# 03_LCD.net
KiCad netlist of a schematic drawn in Altium Designer
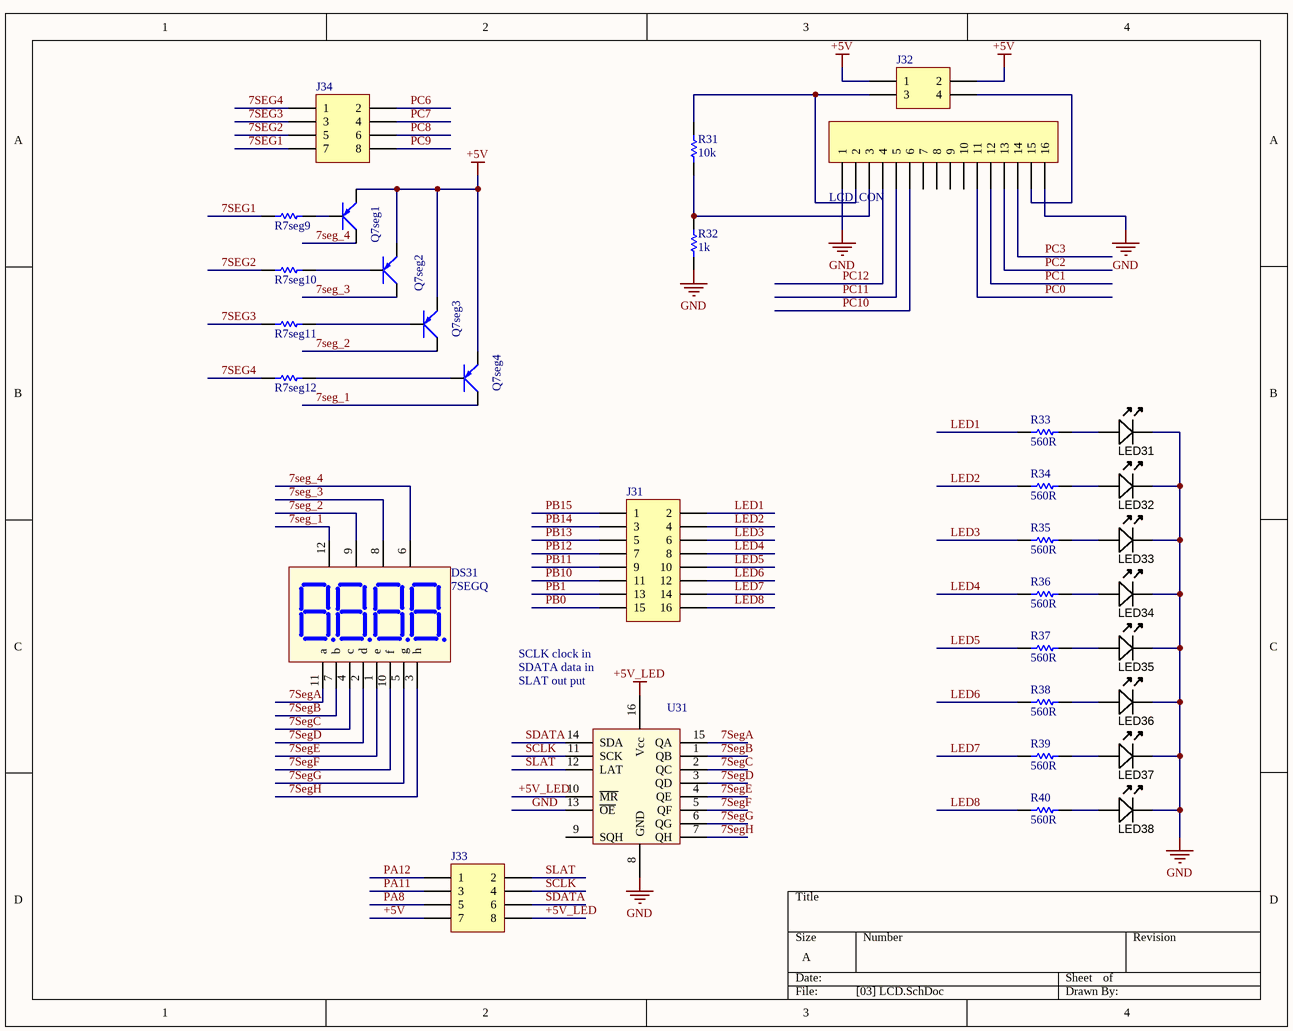
[diagram p0: [03] LCD.SchDoc]

(export (version "E")
  (design (tool "Eeschema 10.0.6"))
  (components
    (comp (ref "DS31")
      (value "7SEGQ")
      (footprint "7segx4_small")
      (description "Four 7 Seg Dipslay")
      (libsource (lib "syhaunguyen") (part "LED7Q"))
    )
    (comp (ref "J31")
      (value "Header 8X2")
      (footprint "HDR2X8")
      (description "Header, 8-Pin, Dual row")
      (fields (field (name "PUBLISHER") "Altium Limited"))
      (libsource (lib "Miscellaneous Connectors") (part "Header 8X2"))
    )
    (comp (ref "J32")
      (value "Header 2X2")
      (footprint "HDR2X2")
      (description "Header, 2-Pin, Dual row")
      (fields (field (name "PUBLISHER") "Altium Limited"))
      (libsource (lib "Miscellaneous Connectors") (part "Header 2X2"))
    )
    (comp (ref "J33")
      (value "Header 4X2")
      (footprint "HDR2X4")
      (description "Header, 4-Pin, Dual row")
      (fields (field (name "PUBLISHER") "Altium Limited"))
      (libsource (lib "Miscellaneous Connectors") (part "Header 4X2"))
    )
    (comp (ref "J34")
      (value "Header 4X2")
      (footprint "HDR2X4")
      (description "Header, 4-Pin, Dual row")
      (fields (field (name "PUBLISHER") "Altium Limited"))
      (libsource (lib "Miscellaneous Connectors") (part "Header 4X2"))
    )
    (comp (ref "LCD_CON")
      (value "Header 16")
      (footprint "HDR1X16")
      (description "Header, 16-Pin")
      (fields (field (name "PUBLISHER") "Altium Limited"))
      (libsource (lib "heromap") (part "Header 16"))
    )
    (comp (ref "LED31")
      (value "Blue")
      (footprint "LED-0805-K")
      (description "LED 0805 SMD Blue 100mcd 470nm")
      (libsource (lib "PBL - Light Sources") (part "LED_SMD_Blue_0805_100mcd"))
    )
    (comp (ref "LED32")
      (value "Blue")
      (footprint "LED-0805-K")
      (description "LED 0805 SMD Blue 100mcd 470nm")
      (libsource (lib "PBL - Light Sources") (part "LED_SMD_Blue_0805_100mcd"))
    )
    (comp (ref "LED33")
      (value "Blue")
      (footprint "LED-0805-K")
      (description "LED 0805 SMD Blue 100mcd 470nm")
      (libsource (lib "PBL - Light Sources") (part "LED_SMD_Blue_0805_100mcd"))
    )
    (comp (ref "LED34")
      (value "Blue")
      (footprint "LED-0805-K")
      (description "LED 0805 SMD Blue 100mcd 470nm")
      (libsource (lib "PBL - Light Sources") (part "LED_SMD_Blue_0805_100mcd"))
    )
    (comp (ref "LED35")
      (value "Blue")
      (footprint "LED-0805-K")
      (description "LED 0805 SMD Blue 100mcd 470nm")
      (libsource (lib "PBL - Light Sources") (part "LED_SMD_Blue_0805_100mcd"))
    )
    (comp (ref "LED36")
      (value "Blue")
      (footprint "LED-0805-K")
      (description "LED 0805 SMD Blue 100mcd 470nm")
      (libsource (lib "PBL - Light Sources") (part "LED_SMD_Blue_0805_100mcd"))
    )
    (comp (ref "LED37")
      (value "Blue")
      (footprint "LED-0805-K")
      (description "LED 0805 SMD Blue 100mcd 470nm")
      (libsource (lib "PBL - Light Sources") (part "LED_SMD_Blue_0805_100mcd"))
    )
    (comp (ref "LED38")
      (value "Blue")
      (footprint "LED-0805-K")
      (description "LED 0805 SMD Blue 100mcd 470nm")
      (libsource (lib "PBL - Light Sources") (part "LED_SMD_Blue_0805_100mcd"))
    )
    (comp (ref "Q7seg1")
      (value "A1015")
      (footprint "SOT23B")
      (description "PNP 600mW, ECB")
      (libsource (lib "syhaunguyen") (part "A1015"))
    )
    (comp (ref "Q7seg2")
      (value "A1015")
      (footprint "SOT23B")
      (description "PNP 600mW, ECB")
      (libsource (lib "syhaunguyen") (part "A1015"))
    )
    (comp (ref "Q7seg3")
      (value "A1015")
      (footprint "SOT23B")
      (description "PNP 600mW, ECB")
      (libsource (lib "syhaunguyen") (part "A1015"))
    )
    (comp (ref "Q7seg4")
      (value "A1015")
      (footprint "SOT23B")
      (description "PNP 600mW, ECB")
      (libsource (lib "syhaunguyen") (part "A1015"))
    )
    (comp (ref "R7seg9") (value "Res") (footprint "RESC1608N_ZERO") (libsource (lib "Tuan") (part "Res")))
    (comp (ref "R7seg10") (value "Res") (footprint "RESC1608N_ZERO") (libsource (lib "Tuan") (part "Res")))
    (comp (ref "R7seg11") (value "Res") (footprint "RESC1608N_ZERO") (libsource (lib "Tuan") (part "Res")))
    (comp (ref "R7seg12") (value "Res") (footprint "RESC1608N_ZERO") (libsource (lib "Tuan") (part "Res")))
    (comp (ref "R31")
      (value "10k")
      (footprint "RESC1608N_ZERO")
      (fields (field (name "Comment") "Res"))
      (libsource (lib "Tuan") (part "Res"))
    )
    (comp (ref "R32")
      (value "1k")
      (footprint "RESC1608N_ZERO")
      (fields (field (name "Comment") "Res"))
      (libsource (lib "Tuan") (part "Res"))
    )
    (comp (ref "R33")
      (value "560R")
      (footprint "RESC1608N_ZERO")
      (fields (field (name "Comment") "Res"))
      (libsource (lib "Tuan") (part "Res"))
    )
    (comp (ref "R34")
      (value "560R")
      (footprint "RESC1608N_ZERO")
      (fields (field (name "Comment") "Res"))
      (libsource (lib "Tuan") (part "Res"))
    )
    (comp (ref "R35")
      (value "560R")
      (footprint "RESC1608N_ZERO")
      (fields (field (name "Comment") "Res"))
      (libsource (lib "Tuan") (part "Res"))
    )
    (comp (ref "R36")
      (value "560R")
      (footprint "RESC1608N_ZERO")
      (fields (field (name "Comment") "Res"))
      (libsource (lib "Tuan") (part "Res"))
    )
    (comp (ref "R37")
      (value "560R")
      (footprint "RESC1608N_ZERO")
      (fields (field (name "Comment") "Res"))
      (libsource (lib "Tuan") (part "Res"))
    )
    (comp (ref "R38")
      (value "560R")
      (footprint "RESC1608N_ZERO")
      (fields (field (name "Comment") "Res"))
      (libsource (lib "Tuan") (part "Res"))
    )
    (comp (ref "R39")
      (value "560R")
      (footprint "RESC1608N_ZERO")
      (fields (field (name "Comment") "Res"))
      (libsource (lib "Tuan") (part "Res"))
    )
    (comp (ref "R40")
      (value "560R")
      (footprint "RESC1608N_ZERO")
      (fields (field (name "Comment") "Res"))
      (libsource (lib "Tuan") (part "Res"))
    )
    (comp (ref "U31") (value "74HC595") (footprint "SOIC16") (libsource (lib "Tuan") (part "74HC595")))
  )
  (nets
    (net (code "1") (name "+5V") (class "Default")
      (node (ref "J32") (pin "1") (pinfunction "1_1") (pintype "passive"))
      (node (ref "J32") (pin "2") (pinfunction "2_2") (pintype "passive"))
      (node (ref "J33") (pin "7") (pinfunction "7_7") (pintype "passive"))
      (node (ref "Q7seg1") (pin "1") (pinfunction "E_1") (pintype "passive"))
      (node (ref "Q7seg2") (pin "1") (pinfunction "E_1") (pintype "passive"))
      (node (ref "Q7seg3") (pin "1") (pinfunction "E_1") (pintype "passive"))
      (node (ref "Q7seg4") (pin "1") (pinfunction "E_1") (pintype "passive"))
    )
    (net (code "2") (name "+5V_LED") (class "Default")
      (node (ref "J33") (pin "8") (pinfunction "8_8") (pintype "passive"))
      (node (ref "U31") (pin "10") (pinfunction "~{MR}_10") (pintype "passive"))
      (node (ref "U31") (pin "16") (pinfunction "Vcc_16") (pintype "power_in"))
    )
    (net (code "3") (name "/7SEG1") (class "Default")
      (node (ref "J34") (pin "7") (pinfunction "7_7") (pintype "passive"))
      (node (ref "R7seg9") (pin "1") (pinfunction "1_1") (pintype "passive"))
    )
    (net (code "4") (name "/7SEG2") (class "Default")
      (node (ref "J34") (pin "5") (pinfunction "5_5") (pintype "passive"))
      (node (ref "R7seg10") (pin "1") (pinfunction "1_1") (pintype "passive"))
    )
    (net (code "5") (name "/7SEG3") (class "Default")
      (node (ref "J34") (pin "3") (pinfunction "3_3") (pintype "passive"))
      (node (ref "R7seg11") (pin "1") (pinfunction "1_1") (pintype "passive"))
    )
    (net (code "6") (name "/7SEG4") (class "Default")
      (node (ref "J34") (pin "1") (pinfunction "1_1") (pintype "passive"))
      (node (ref "R7seg12") (pin "1") (pinfunction "1_1") (pintype "passive"))
    )
    (net (code "7") (name "/7SegA") (class "Default")
      (node (ref "DS31") (pin "11") (pinfunction "a_11") (pintype "passive"))
      (node (ref "U31") (pin "15") (pinfunction "QA_15") (pintype "passive"))
    )
    (net (code "8") (name "/7SegB") (class "Default")
      (node (ref "DS31") (pin "7") (pinfunction "b_7") (pintype "passive"))
      (node (ref "U31") (pin "1") (pinfunction "QB_1") (pintype "passive"))
    )
    (net (code "9") (name "/7SegC") (class "Default")
      (node (ref "DS31") (pin "4") (pinfunction "c_4") (pintype "passive"))
      (node (ref "U31") (pin "2") (pinfunction "QC_2") (pintype "passive"))
    )
    (net (code "10") (name "/7SegD") (class "Default")
      (node (ref "DS31") (pin "2") (pinfunction "d_2") (pintype "passive"))
      (node (ref "U31") (pin "3") (pinfunction "QD_3") (pintype "passive"))
    )
    (net (code "11") (name "/7SegE") (class "Default")
      (node (ref "DS31") (pin "1") (pinfunction "e_1") (pintype "passive"))
      (node (ref "U31") (pin "4") (pinfunction "QE_4") (pintype "passive"))
    )
    (net (code "12") (name "/7SegF") (class "Default")
      (node (ref "DS31") (pin "10") (pinfunction "f_10") (pintype "passive"))
      (node (ref "U31") (pin "5") (pinfunction "QF_5") (pintype "passive"))
    )
    (net (code "13") (name "/7SegG") (class "Default")
      (node (ref "DS31") (pin "5") (pinfunction "g_5") (pintype "passive"))
      (node (ref "U31") (pin "6") (pinfunction "QG_6") (pintype "passive"))
    )
    (net (code "14") (name "/7SegH") (class "Default")
      (node (ref "DS31") (pin "3") (pinfunction "h_3") (pintype "passive"))
      (node (ref "U31") (pin "7") (pinfunction "QH_7") (pintype "passive"))
    )
    (net (code "15") (name "/7seg_1") (class "Default")
      (node (ref "DS31") (pin "12") (pinfunction "V1_12") (pintype "passive"))
      (node (ref "Q7seg4") (pin "2") (pinfunction "C_2") (pintype "passive"))
    )
    (net (code "16") (name "/7seg_2") (class "Default")
      (node (ref "DS31") (pin "9") (pinfunction "V2_9") (pintype "passive"))
      (node (ref "Q7seg3") (pin "2") (pinfunction "C_2") (pintype "passive"))
    )
    (net (code "17") (name "/7seg_3") (class "Default")
      (node (ref "DS31") (pin "8") (pinfunction "V3_8") (pintype "passive"))
      (node (ref "Q7seg2") (pin "2") (pinfunction "C_2") (pintype "passive"))
    )
    (net (code "18") (name "/7seg_4") (class "Default")
      (node (ref "DS31") (pin "6") (pinfunction "V4_6") (pintype "passive"))
      (node (ref "Q7seg1") (pin "2") (pinfunction "C_2") (pintype "passive"))
    )
    (net (code "19") (name "/LED1") (class "Default")
      (node (ref "J31") (pin "2") (pinfunction "2_2") (pintype "passive"))
      (node (ref "R33") (pin "1") (pinfunction "1_1") (pintype "passive"))
    )
    (net (code "20") (name "/LED2") (class "Default")
      (node (ref "J31") (pin "4") (pinfunction "4_4") (pintype "passive"))
      (node (ref "R34") (pin "1") (pinfunction "1_1") (pintype "passive"))
    )
    (net (code "21") (name "/LED3") (class "Default")
      (node (ref "J31") (pin "6") (pinfunction "6_6") (pintype "passive"))
      (node (ref "R35") (pin "1") (pinfunction "1_1") (pintype "passive"))
    )
    (net (code "22") (name "/LED4") (class "Default")
      (node (ref "J31") (pin "8") (pinfunction "8_8") (pintype "passive"))
      (node (ref "R36") (pin "1") (pinfunction "1_1") (pintype "passive"))
    )
    (net (code "23") (name "/LED5") (class "Default")
      (node (ref "J31") (pin "10") (pinfunction "10_10") (pintype "passive"))
      (node (ref "R37") (pin "1") (pinfunction "1_1") (pintype "passive"))
    )
    (net (code "24") (name "/LED6") (class "Default")
      (node (ref "J31") (pin "12") (pinfunction "12_12") (pintype "passive"))
      (node (ref "R38") (pin "1") (pinfunction "1_1") (pintype "passive"))
    )
    (net (code "25") (name "/LED7") (class "Default")
      (node (ref "J31") (pin "14") (pinfunction "14_14") (pintype "passive"))
      (node (ref "R39") (pin "1") (pinfunction "1_1") (pintype "passive"))
    )
    (net (code "26") (name "/LED8") (class "Default")
      (node (ref "J31") (pin "16") (pinfunction "16_16") (pintype "passive"))
      (node (ref "R40") (pin "1") (pinfunction "1_1") (pintype "passive"))
    )
    (net (code "27") (name "/PA8") (class "Default")
      (node (ref "J33") (pin "5") (pinfunction "5_5") (pintype "passive"))
    )
    (net (code "28") (name "/PA11") (class "Default")
      (node (ref "J33") (pin "3") (pinfunction "3_3") (pintype "passive"))
    )
    (net (code "29") (name "/PA12") (class "Default")
      (node (ref "J33") (pin "1") (pinfunction "1_1") (pintype "passive"))
    )
    (net (code "30") (name "/PB0") (class "Default")
      (node (ref "J31") (pin "15") (pinfunction "15_15") (pintype "passive"))
    )
    (net (code "31") (name "/PB1") (class "Default")
      (node (ref "J31") (pin "13") (pinfunction "13_13") (pintype "passive"))
    )
    (net (code "32") (name "/PB10") (class "Default")
      (node (ref "J31") (pin "11") (pinfunction "11_11") (pintype "passive"))
    )
    (net (code "33") (name "/PB11") (class "Default")
      (node (ref "J31") (pin "9") (pinfunction "9_9") (pintype "passive"))
    )
    (net (code "34") (name "/PB12") (class "Default")
      (node (ref "J31") (pin "7") (pinfunction "7_7") (pintype "passive"))
    )
    (net (code "35") (name "/PB13") (class "Default")
      (node (ref "J31") (pin "5") (pinfunction "5_5") (pintype "passive"))
    )
    (net (code "36") (name "/PB14") (class "Default")
      (node (ref "J31") (pin "3") (pinfunction "3_3") (pintype "passive"))
    )
    (net (code "37") (name "/PB15") (class "Default")
      (node (ref "J31") (pin "1") (pinfunction "1_1") (pintype "passive"))
    )
    (net (code "38") (name "/PC0") (class "Default")
      (node (ref "LCD_CON") (pin "11") (pinfunction "11_11") (pintype "passive"))
    )
    (net (code "39") (name "/PC1") (class "Default")
      (node (ref "LCD_CON") (pin "12") (pinfunction "12_12") (pintype "passive"))
    )
    (net (code "40") (name "/PC2") (class "Default")
      (node (ref "LCD_CON") (pin "13") (pinfunction "13_13") (pintype "passive"))
    )
    (net (code "41") (name "/PC3") (class "Default")
      (node (ref "LCD_CON") (pin "14") (pinfunction "14_14") (pintype "passive"))
    )
    (net (code "42") (name "/PC6") (class "Default")
      (node (ref "J34") (pin "2") (pinfunction "2_2") (pintype "passive"))
    )
    (net (code "43") (name "/PC7") (class "Default")
      (node (ref "J34") (pin "4") (pinfunction "4_4") (pintype "passive"))
    )
    (net (code "44") (name "/PC8") (class "Default")
      (node (ref "J34") (pin "6") (pinfunction "6_6") (pintype "passive"))
    )
    (net (code "45") (name "/PC9") (class "Default")
      (node (ref "J34") (pin "8") (pinfunction "8_8") (pintype "passive"))
    )
    (net (code "46") (name "/PC10") (class "Default")
      (node (ref "LCD_CON") (pin "6") (pinfunction "6_6") (pintype "passive"))
    )
    (net (code "47") (name "/PC11") (class "Default")
      (node (ref "LCD_CON") (pin "5") (pinfunction "5_5") (pintype "passive"))
    )
    (net (code "48") (name "/PC12") (class "Default")
      (node (ref "LCD_CON") (pin "4") (pinfunction "4_4") (pintype "passive"))
    )
    (net (code "49") (name "/SCLK") (class "Default")
      (node (ref "J33") (pin "4") (pinfunction "4_4") (pintype "passive"))
      (node (ref "U31") (pin "11") (pinfunction "SCK_11") (pintype "passive"))
    )
    (net (code "50") (name "/SDATA") (class "Default")
      (node (ref "J33") (pin "6") (pinfunction "6_6") (pintype "passive"))
      (node (ref "U31") (pin "14") (pinfunction "SDA_14") (pintype "passive"))
    )
    (net (code "51") (name "/SLAT") (class "Default")
      (node (ref "J33") (pin "2") (pinfunction "2_2") (pintype "passive"))
      (node (ref "U31") (pin "12") (pinfunction "LAT_12") (pintype "passive"))
    )
    (net (code "52") (name "GND") (class "Default")
      (node (ref "LCD_CON") (pin "1") (pinfunction "1_1") (pintype "passive"))
      (node (ref "LCD_CON") (pin "16") (pinfunction "16_16") (pintype "passive"))
      (node (ref "LED31") (pin "K") (pinfunction "K_K") (pintype "passive"))
      (node (ref "LED32") (pin "K") (pinfunction "K_K") (pintype "passive"))
      (node (ref "LED33") (pin "K") (pinfunction "K_K") (pintype "passive"))
      (node (ref "LED34") (pin "K") (pinfunction "K_K") (pintype "passive"))
      (node (ref "LED35") (pin "K") (pinfunction "K_K") (pintype "passive"))
      (node (ref "LED36") (pin "K") (pinfunction "K_K") (pintype "passive"))
      (node (ref "LED37") (pin "K") (pinfunction "K_K") (pintype "passive"))
      (node (ref "LED38") (pin "K") (pinfunction "K_K") (pintype "passive"))
      (node (ref "R32") (pin "1") (pinfunction "1_1") (pintype "passive"))
      (node (ref "U31") (pin "13") (pinfunction "~{OE}_13") (pintype "passive"))
      (node (ref "U31") (pin "8") (pinfunction "GND_8") (pintype "power_in"))
    )
    (net (code "53") (name "Net-(J32-Pad3)") (class "Default")
      (node (ref "J32") (pin "3") (pinfunction "3_3") (pintype "passive"))
      (node (ref "LCD_CON") (pin "2") (pinfunction "2_2") (pintype "passive"))
      (node (ref "R31") (pin "2") (pinfunction "2_2") (pintype "passive"))
    )
    (net (code "54") (name "Net-(J32-Pad4)") (class "Default")
      (node (ref "J32") (pin "4") (pinfunction "4_4") (pintype "passive"))
      (node (ref "LCD_CON") (pin "15") (pinfunction "15_15") (pintype "passive"))
    )
    (net (code "55") (name "Net-(LCD_CON-Pad3)") (class "Default")
      (node (ref "LCD_CON") (pin "3") (pinfunction "3_3") (pintype "passive"))
      (node (ref "R31") (pin "1") (pinfunction "1_1") (pintype "passive"))
      (node (ref "R32") (pin "2") (pinfunction "2_2") (pintype "passive"))
    )
    (net (code "56") (name "Net-(LED31-PadA)") (class "Default")
      (node (ref "LED31") (pin "A") (pinfunction "A_A") (pintype "passive"))
      (node (ref "R33") (pin "2") (pinfunction "2_2") (pintype "passive"))
    )
    (net (code "57") (name "Net-(LED32-PadA)") (class "Default")
      (node (ref "LED32") (pin "A") (pinfunction "A_A") (pintype "passive"))
      (node (ref "R34") (pin "2") (pinfunction "2_2") (pintype "passive"))
    )
    (net (code "58") (name "Net-(LED33-PadA)") (class "Default")
      (node (ref "LED33") (pin "A") (pinfunction "A_A") (pintype "passive"))
      (node (ref "R35") (pin "2") (pinfunction "2_2") (pintype "passive"))
    )
    (net (code "59") (name "Net-(LED34-PadA)") (class "Default")
      (node (ref "LED34") (pin "A") (pinfunction "A_A") (pintype "passive"))
      (node (ref "R36") (pin "2") (pinfunction "2_2") (pintype "passive"))
    )
    (net (code "60") (name "Net-(LED35-PadA)") (class "Default")
      (node (ref "LED35") (pin "A") (pinfunction "A_A") (pintype "passive"))
      (node (ref "R37") (pin "2") (pinfunction "2_2") (pintype "passive"))
    )
    (net (code "61") (name "Net-(LED36-PadA)") (class "Default")
      (node (ref "LED36") (pin "A") (pinfunction "A_A") (pintype "passive"))
      (node (ref "R38") (pin "2") (pinfunction "2_2") (pintype "passive"))
    )
    (net (code "62") (name "Net-(LED37-PadA)") (class "Default")
      (node (ref "LED37") (pin "A") (pinfunction "A_A") (pintype "passive"))
      (node (ref "R39") (pin "2") (pinfunction "2_2") (pintype "passive"))
    )
    (net (code "63") (name "Net-(LED38-PadA)") (class "Default")
      (node (ref "LED38") (pin "A") (pinfunction "A_A") (pintype "passive"))
      (node (ref "R40") (pin "2") (pinfunction "2_2") (pintype "passive"))
    )
    (net (code "64") (name "Net-(Q7seg1-B)") (class "Default")
      (node (ref "Q7seg1") (pin "3") (pinfunction "B_3") (pintype "passive"))
      (node (ref "R7seg9") (pin "2") (pinfunction "2_2") (pintype "passive"))
    )
    (net (code "65") (name "Net-(Q7seg2-B)") (class "Default")
      (node (ref "Q7seg2") (pin "3") (pinfunction "B_3") (pintype "passive"))
      (node (ref "R7seg10") (pin "2") (pinfunction "2_2") (pintype "passive"))
    )
    (net (code "66") (name "Net-(Q7seg3-B)") (class "Default")
      (node (ref "Q7seg3") (pin "3") (pinfunction "B_3") (pintype "passive"))
      (node (ref "R7seg11") (pin "2") (pinfunction "2_2") (pintype "passive"))
    )
    (net (code "67") (name "Net-(Q7seg4-B)") (class "Default")
      (node (ref "Q7seg4") (pin "3") (pinfunction "B_3") (pintype "passive"))
      (node (ref "R7seg12") (pin "2") (pinfunction "2_2") (pintype "passive"))
    )
    (net (code "68") (name "unconnected-(LCD_CON-Pad7)") (class "Default")
      (node (ref "LCD_CON") (pin "7") (pinfunction "7_7") (pintype "passive"))
    )
    (net (code "69") (name "unconnected-(LCD_CON-Pad8)") (class "Default")
      (node (ref "LCD_CON") (pin "8") (pinfunction "8_8") (pintype "passive"))
    )
    (net (code "70") (name "unconnected-(LCD_CON-Pad9)") (class "Default")
      (node (ref "LCD_CON") (pin "9") (pinfunction "9_9") (pintype "passive"))
    )
    (net (code "71") (name "unconnected-(LCD_CON-Pad10)") (class "Default")
      (node (ref "LCD_CON") (pin "10") (pinfunction "10_10") (pintype "passive"))
    )
    (net (code "72") (name "unconnected-(U31-SQH-Pad9)") (class "Default")
      (node (ref "U31") (pin "9") (pinfunction "SQH_9") (pintype "passive"))
    )
  )
)
